# LabAccessBoard.net
KiCad netlist of a schematic drawn in EAGLE
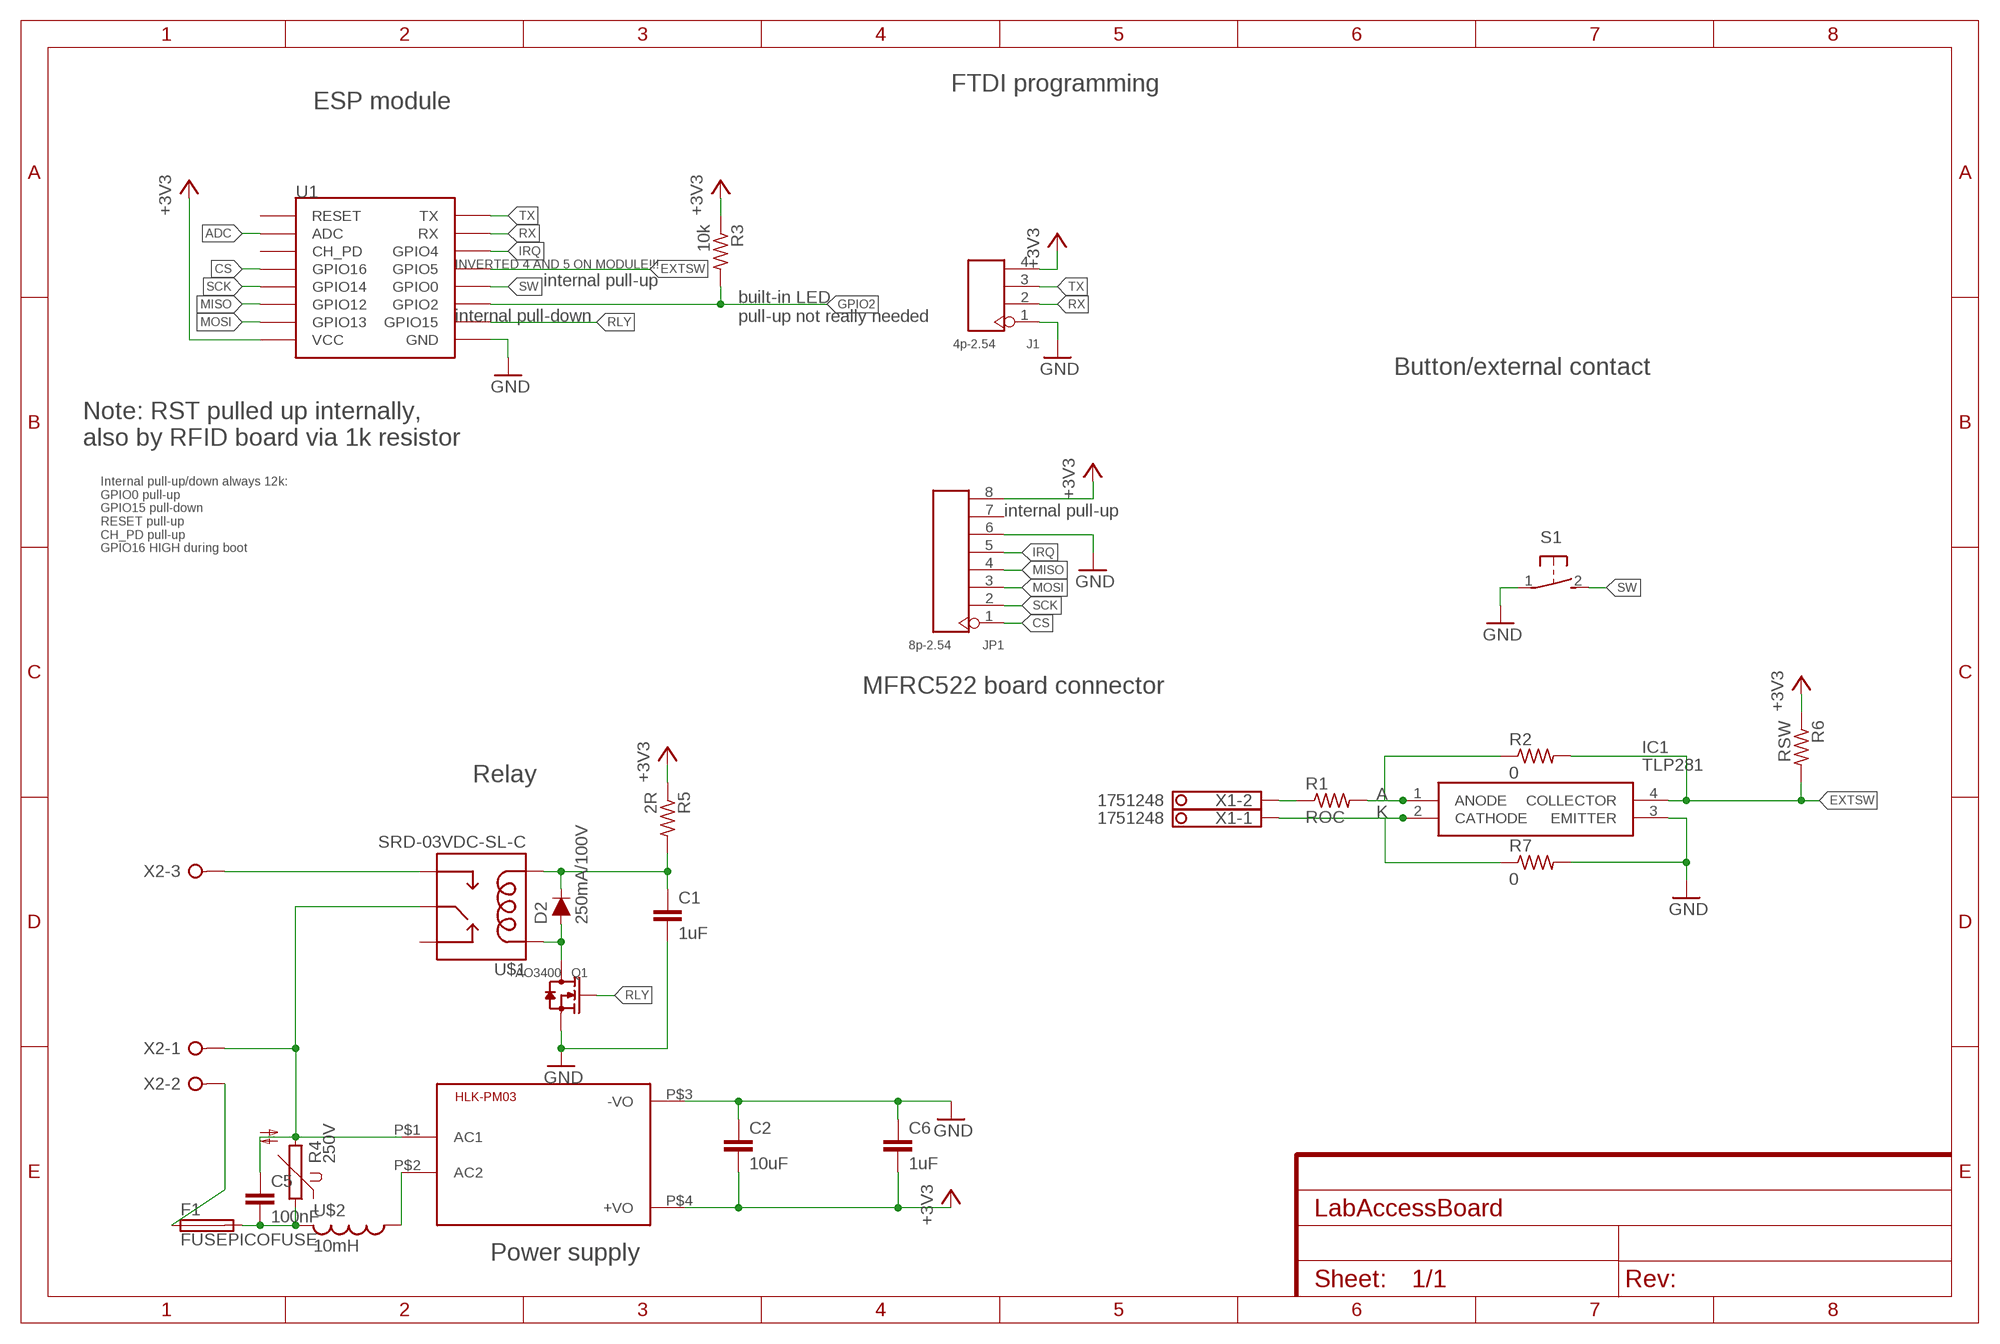
[diagram p0: schematic, sheet 1]

(export (version "E")
  (design (tool "Eeschema 10.0.6"))
  (components
    (comp (ref "C1")
      (value "1uF")
      (footprint "eagle-import:C0603K")
      (libsource (lib "eagle-import") (part "C-EUC0603K"))
    )
    (comp (ref "C2")
      (value "10uF")
      (footprint "eagle-import:C0805K")
      (libsource (lib "eagle-import") (part "C-EUC0805K"))
    )
    (comp (ref "C5")
      (value "100nF")
      (footprint "eagle-import:C102-064X133")
      (libsource (lib "eagle-import") (part "C-EU102-064X133"))
    )
    (comp (ref "C6")
      (value "1uF")
      (footprint "eagle-import:C0603K")
      (libsource (lib "eagle-import") (part "C-EUC0603K"))
    )
    (comp (ref "D2")
      (value "250mA/100V")
      (footprint "eagle-import:SOD-323")
      (libsource (lib "eagle-import") (part "DIODE-BAS16J"))
    )
    (comp (ref "F1")
      (value "FUSEPICOFUSE")
      (footprint "eagle-import:PICOFUSE")
      (libsource (lib "eagle-import") (part "FUSEPICOFUSE"))
    )
    (comp (ref "HLK-PM03")
      (value "HLK-PM03")
      (footprint "eagle-import:HLK-PM01")
      (libsource (lib "eagle-import") (part "HLK-PM013W"))
    )
    (comp (ref "IC1")
      (value "TLP281")
      (footprint "eagle-import:SOIC127P700X190-4N")
      (fields (field (name "ARROW_PART_NUMBER") "TLP281(GB-TP,F)"))
      (libsource (lib "eagle-import") (part "TLP281(GB-TP,F)"))
    )
    (comp (ref "J1")
      (value "4p-2.54")
      (footprint "eagle-import:H4-2.54")
      (fields (field (name "MPN") "P125-1104A0BS116A1"))
      (libsource (lib "eagle-import") (part "DIP-BLACK-MALE-HEADER-VERT(4P-2.54)"))
    )
    (comp (ref "JP1")
      (value "8p-2.54")
      (footprint "eagle-import:H8-2.54")
      (fields (field (name "MPN") "P125-1108A1BS116A1"))
      (libsource (lib "eagle-import") (part "DIP-BLACK-MALE-HEADER-VERT(8P-2.54)"))
    )
    (comp (ref "Q1")
      (value "AO3400")
      (footprint "eagle-import:SOT-23")
      (fields (field (name "MPN") "2N7002,215"))
      (libsource (lib "eagle-import") (part "SMD-MOSFET-N-CH-60V-300MA-LOGIC-LEVEL-FET-2N7002(SOT-23)"))
    )
    (comp (ref "R1")
      (value "ROC")
      (footprint "eagle-import:R0603")
      (libsource (lib "eagle-import") (part "R-US_R0603"))
    )
    (comp (ref "R2")
      (value "0")
      (footprint "eagle-import:R0603")
      (libsource (lib "eagle-import") (part "R-US_R0603"))
    )
    (comp (ref "R3")
      (value "10k")
      (footprint "eagle-import:R0603")
      (libsource (lib "eagle-import") (part "R-US_R0603"))
    )
    (comp (ref "R4")
      (value "250V")
      (footprint "eagle-import:S07K250")
      (libsource (lib "eagle-import") (part "S07K250"))
    )
    (comp (ref "R5")
      (value "2R")
      (footprint "eagle-import:R0603")
      (libsource (lib "eagle-import") (part "R-US_R0603"))
    )
    (comp (ref "R6")
      (value "RSW")
      (footprint "eagle-import:R0603")
      (libsource (lib "eagle-import") (part "R-US_R0603"))
    )
    (comp (ref "R7")
      (value "0")
      (footprint "eagle-import:R0603")
      (libsource (lib "eagle-import") (part "R-US_R0603"))
    )
    (comp (ref "S1")
      (value "31-XX")
      (footprint "eagle-import:B3F-31XX")
      (fields (field (name "MPN") "B3F-3100"))
      (libsource (lib "eagle-import") (part "31-XX"))
    )
    (comp (ref "U$1")
      (value "SRD-03VDC-SL-C")
      (footprint "eagle-import:SRD-0XVDC-SL-C")
      (libsource (lib "eagle-import") (part "SRD-0XVDC-SL-CSRD-06VDC-SL-C"))
    )
    (comp (ref "U$2")
      (value "10mH")
      (footprint "eagle-import:6000-XXXX-RC")
      (libsource (lib "eagle-import") (part "L-US6000-XXX-RC"))
    )
    (comp (ref "U1")
      (value "ESP12SMD")
      (footprint "eagle-import:ESP12-SMD")
      (libsource (lib "eagle-import") (part "ESP12SMD"))
    )
    (comp (ref "X1")
      (value "1751248")
      (footprint "eagle-import:1751248")
      (libsource (lib "eagle-import") (part "1751248"))
    )
    (comp (ref "X2")
      (value "W237-3E")
      (footprint "eagle-import:W237-3E")
      (libsource (lib "eagle-import") (part "W237-3E"))
    )
  )
  (nets
    (net (code "1") (name "+3V3") (class "Default")
      (node (ref "C2") (pin "2") (pinfunction "2_2") (pintype "passive"))
      (node (ref "C6") (pin "2") (pinfunction "2_2") (pintype "passive"))
      (node (ref "HLK-PM03") (pin "P$4") (pinfunction "+VO_P$4") (pintype "bidirectional"))
      (node (ref "J1") (pin "4") (pinfunction "P$4_4") (pintype "bidirectional"))
      (node (ref "JP1") (pin "8") (pinfunction "8_8") (pintype "bidirectional"))
      (node (ref "R3") (pin "1") (pinfunction "1_1") (pintype "passive"))
      (node (ref "R5") (pin "1") (pinfunction "1_1") (pintype "passive"))
      (node (ref "R6") (pin "1") (pinfunction "1_1") (pintype "passive"))
      (node (ref "U1") (pin "VCC") (pinfunction "VCC_VCC") (pintype "bidirectional"))
    )
    (net (code "2") (name "/A") (class "Default")
      (node (ref "IC1") (pin "1") (pinfunction "ANODE_1") (pintype "bidirectional"))
      (node (ref "R1") (pin "2") (pinfunction "2_2") (pintype "passive"))
      (node (ref "R2") (pin "1") (pinfunction "1_1") (pintype "passive"))
    )
    (net (code "3") (name "/K") (class "Default")
      (node (ref "IC1") (pin "2") (pinfunction "CATHODE_2") (pintype "bidirectional"))
      (node (ref "R7") (pin "1") (pinfunction "1_1") (pintype "passive"))
      (node (ref "X1") (pin "1") (pinfunction "K_1") (pintype "passive"))
    )
    (net (code "4") (name "ADC") (class "Default")
      (node (ref "U1") (pin "ADC") (pinfunction "ADC_ADC") (pintype "bidirectional"))
    )
    (net (code "5") (name "CS") (class "Default")
      (node (ref "JP1") (pin "1") (pinfunction "1_1") (pintype "bidirectional"))
      (node (ref "U1") (pin "GPIO16") (pinfunction "GPIO16_GPIO16") (pintype "bidirectional"))
    )
    (net (code "6") (name "EXTSW") (class "Default")
      (node (ref "IC1") (pin "4") (pinfunction "COLLECTOR_4") (pintype "bidirectional"))
      (node (ref "R2") (pin "2") (pinfunction "2_2") (pintype "passive"))
      (node (ref "R6") (pin "2") (pinfunction "2_2") (pintype "passive"))
      (node (ref "U1") (pin "GPIO5") (pinfunction "GPIO5_GPIO5") (pintype "bidirectional"))
    )
    (net (code "7") (name "GND") (class "Default")
      (node (ref "C1") (pin "2") (pinfunction "2_2") (pintype "passive"))
      (node (ref "C2") (pin "1") (pinfunction "1_1") (pintype "passive"))
      (node (ref "C6") (pin "1") (pinfunction "1_1") (pintype "passive"))
      (node (ref "HLK-PM03") (pin "P$3") (pinfunction "-VO_P$3") (pintype "bidirectional"))
      (node (ref "IC1") (pin "3") (pinfunction "EMITTER_3") (pintype "bidirectional"))
      (node (ref "J1") (pin "1") (pinfunction "P$1_1") (pintype "bidirectional"))
      (node (ref "JP1") (pin "6") (pinfunction "6_6") (pintype "bidirectional"))
      (node (ref "Q1") (pin "2") (pinfunction "S_2") (pintype "passive"))
      (node (ref "R7") (pin "2") (pinfunction "2_2") (pintype "passive"))
      (node (ref "S1") (pin "1") (pinfunction "P_1") (pintype "passive"))
      (node (ref "U1") (pin "GND") (pinfunction "GND_GND") (pintype "bidirectional"))
    )
    (net (code "8") (name "GPIO2") (class "Default")
      (node (ref "R3") (pin "2") (pinfunction "2_2") (pintype "passive"))
      (node (ref "U1") (pin "GPIO2") (pinfunction "GPIO2_GPIO2") (pintype "bidirectional"))
    )
    (net (code "9") (name "IRQ") (class "Default")
      (node (ref "JP1") (pin "5") (pinfunction "5_5") (pintype "bidirectional"))
      (node (ref "U1") (pin "GPIO4") (pinfunction "GPIO4_GPIO4") (pintype "bidirectional"))
    )
    (net (code "10") (name "MISO") (class "Default")
      (node (ref "JP1") (pin "4") (pinfunction "4_4") (pintype "bidirectional"))
      (node (ref "U1") (pin "GPIO12") (pinfunction "GPIO12_GPIO12") (pintype "bidirectional"))
    )
    (net (code "11") (name "MOSI") (class "Default")
      (node (ref "JP1") (pin "3") (pinfunction "3_3") (pintype "bidirectional"))
      (node (ref "U1") (pin "GPIO13") (pinfunction "GPIO13_GPIO13") (pintype "bidirectional"))
    )
    (net (code "12") (name "Net-(C1-Pad1)") (class "Default")
      (node (ref "C1") (pin "1") (pinfunction "1_1") (pintype "passive"))
      (node (ref "D2") (pin "C") (pinfunction "C_C") (pintype "passive"))
      (node (ref "R5") (pin "2") (pinfunction "2_2") (pintype "passive"))
      (node (ref "U$1") (pin "COIL0") (pinfunction "COIL0_COIL0") (pintype "bidirectional"))
    )
    (net (code "13") (name "Net-(C5-Pad2)") (class "Default")
      (node (ref "C5") (pin "2") (pinfunction "2_2") (pintype "passive"))
      (node (ref "F1") (pin "2") (pinfunction "2_2") (pintype "passive"))
      (node (ref "R4") (pin "1") (pinfunction "1_1") (pintype "passive"))
      (node (ref "U$2") (pin "2") (pinfunction "2_2") (pintype "passive"))
    )
    (net (code "14") (name "Net-(HLK-PM03-AC1)") (class "Default")
      (node (ref "C5") (pin "1") (pinfunction "1_1") (pintype "passive"))
      (node (ref "HLK-PM03") (pin "P$1") (pinfunction "AC1_P$1") (pintype "bidirectional"))
      (node (ref "R4") (pin "2") (pinfunction "2_2") (pintype "passive"))
      (node (ref "U$1") (pin "SWCOMMON") (pinfunction "SWCOMMON_SWCOMMON") (pintype "bidirectional"))
      (node (ref "X2") (pin "1") (pinfunction "KL_1") (pintype "passive"))
    )
    (net (code "15") (name "Net-(HLK-PM03-AC2)") (class "Default")
      (node (ref "HLK-PM03") (pin "P$2") (pinfunction "AC2_P$2") (pintype "bidirectional"))
      (node (ref "U$2") (pin "1") (pinfunction "1_1") (pintype "passive"))
    )
    (net (code "16") (name "Net-(Q1-D)") (class "Default")
      (node (ref "D2") (pin "A") (pinfunction "A_A") (pintype "passive"))
      (node (ref "Q1") (pin "3") (pinfunction "D_3") (pintype "passive"))
      (node (ref "U$1") (pin "COIL1") (pinfunction "COIL1_COIL1") (pintype "bidirectional"))
    )
    (net (code "17") (name "Net-(X1B-K)") (class "Default")
      (node (ref "R1") (pin "1") (pinfunction "1_1") (pintype "passive"))
      (node (ref "X1") (pin "2") (pinfunction "K_2") (pintype "passive"))
    )
    (net (code "18") (name "Net-(X2B-KL)") (class "Default")
      (node (ref "F1") (pin "1") (pinfunction "1_1") (pintype "passive"))
      (node (ref "X2") (pin "2") (pinfunction "KL_2") (pintype "passive"))
    )
    (net (code "19") (name "Net-(X2C-KL)") (class "Default")
      (node (ref "U$1") (pin "SWOPEN") (pinfunction "SWOPEN_SWOPEN") (pintype "bidirectional"))
      (node (ref "X2") (pin "3") (pinfunction "KL_3") (pintype "passive"))
    )
    (net (code "20") (name "RLY") (class "Default")
      (node (ref "Q1") (pin "1") (pinfunction "G_1") (pintype "passive"))
      (node (ref "U1") (pin "GPIO15") (pinfunction "GPIO15_GPIO15") (pintype "bidirectional"))
    )
    (net (code "21") (name "RX") (class "Default")
      (node (ref "J1") (pin "2") (pinfunction "P$2_2") (pintype "bidirectional"))
      (node (ref "U1") (pin "RXD0") (pinfunction "RX_RXD0") (pintype "bidirectional"))
    )
    (net (code "22") (name "SCK") (class "Default")
      (node (ref "JP1") (pin "2") (pinfunction "2_2") (pintype "bidirectional"))
      (node (ref "U1") (pin "GPIO14") (pinfunction "GPIO14_GPIO14") (pintype "bidirectional"))
    )
    (net (code "23") (name "SW") (class "Default")
      (node (ref "S1") (pin "2") (pinfunction "S_2") (pintype "passive"))
      (node (ref "U1") (pin "GPIO0") (pinfunction "GPIO0_GPIO0") (pintype "bidirectional"))
    )
    (net (code "24") (name "TX") (class "Default")
      (node (ref "J1") (pin "3") (pinfunction "P$3_3") (pintype "bidirectional"))
      (node (ref "U1") (pin "TXD0") (pinfunction "TX_TXD0") (pintype "bidirectional"))
    )
    (net (code "25") (name "unconnected-(JP1-Pad7)") (class "Default")
      (node (ref "JP1") (pin "7") (pinfunction "7_7") (pintype "bidirectional"))
    )
    (net (code "26") (name "unconnected-(U$1-SWCLOSE-PadSWCLOSED)") (class "Default")
      (node (ref "U$1") (pin "SWCLOSED") (pinfunction "SWCLOSE_SWCLOSED") (pintype "bidirectional"))
    )
    (net (code "27") (name "unconnected-(U1-PadCH_PD)") (class "Default")
      (node (ref "U1") (pin "CH_PD") (pinfunction "CH_PD_CH_PD") (pintype "bidirectional"))
    )
    (net (code "28") (name "unconnected-(U1-PadRESET)") (class "Default")
      (node (ref "U1") (pin "RESET") (pinfunction "RESET_RESET") (pintype "bidirectional"))
    )
  )
)
